# main.net
KiCad netlist of a schematic drawn in Altium Designer
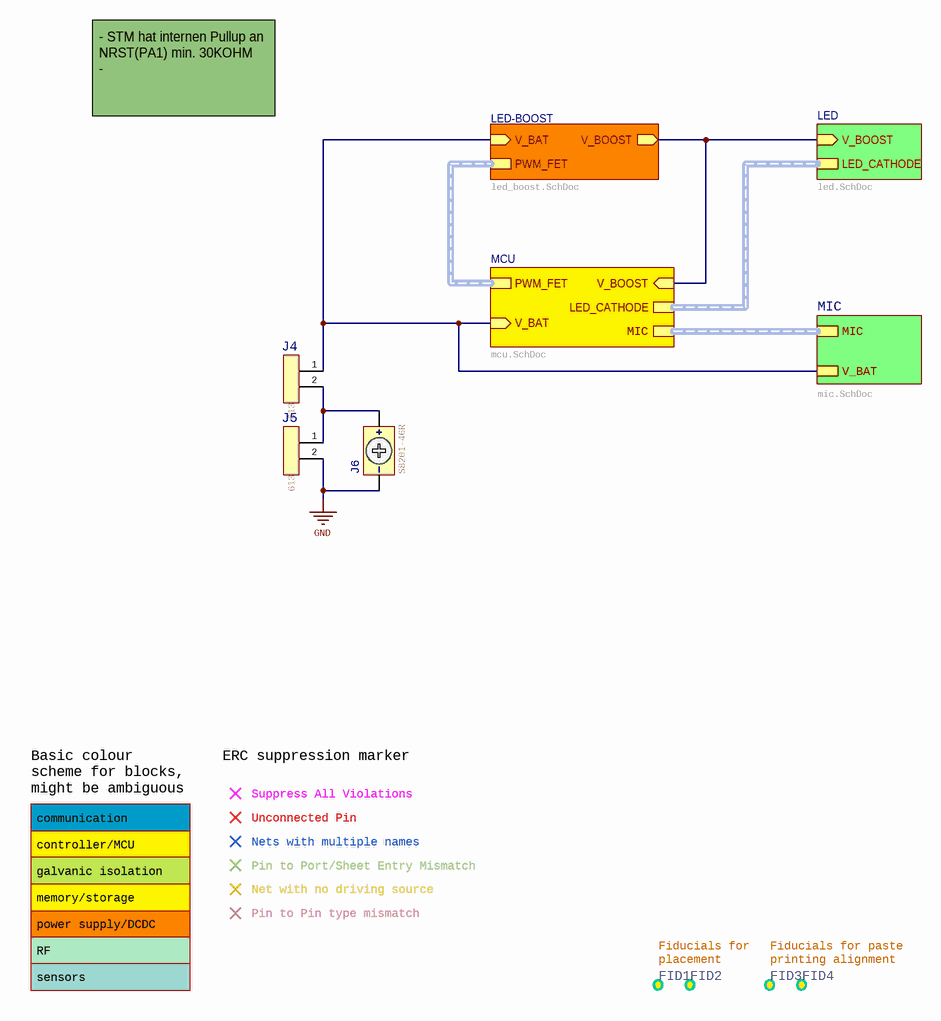
[diagram p0: main.SchDoc]

(export (version "E")
  (design (tool "Eeschema 10.0.6"))
  (components
    (comp (ref "FID1")
      (value "FIDUCIAL")
      (footprint "FID-1MM-0.5MM")
      (description "Fiducial Mark, 1mm diameter, 0.5mm clearance")
      (libsource (lib "Contronix") (part "FIDUCIAL"))
    )
    (comp (ref "FID2")
      (value "FIDUCIAL")
      (footprint "FID-1MM-0.5MM")
      (description "Fiducial Mark, 1mm diameter, 0.5mm clearance")
      (libsource (lib "Contronix") (part "FIDUCIAL"))
    )
    (comp (ref "FID3")
      (value "FIDUCIAL-CIRCLE-PASTE")
      (footprint "FID-1MM-0.5MM-PASTE")
      (description "Fiducial Mark, 1mm circle0.5mm clearance, Pastemask open")
      (libsource (lib "Contronix") (part "FIDUCIAL-CIRCLE-PASTE"))
    )
    (comp (ref "FID4")
      (value "FIDUCIAL-CIRCLE-PASTE")
      (footprint "FID-1MM-0.5MM-PASTE")
      (description "Fiducial Mark, 1mm circle0.5mm clearance, Pastemask open")
      (libsource (lib "Contronix") (part "FIDUCIAL-CIRCLE-PASTE"))
    )
    (comp (ref "J4")
      (value "CON-02")
      (footprint "CON-02-1-254-V-T-PFL-Jumper")
      (description "Stiftleiste, 2-polig, 2.54mm, +Jumper")
      (fields
        (field (name "MANUFACTURER P/N") "61300211121")
        (field (name "MANUFACTURER") "Würth Elektronik")
        (field (name "MANUFACTURER PART NUMBER") "61300211121")
      )
      (libsource (lib "Contronix") (part "CON-02"))
    )
    (comp (ref "J5")
      (value "CON-02")
      (footprint "CON-02-1-254-V-T-PFL-Jumper")
      (description "Stiftleiste, 2-polig, 2.54mm, +Jumper")
      (fields
        (field (name "MANUFACTURER P/N") "61300211121")
        (field (name "MANUFACTURER") "Würth Elektronik")
        (field (name "MANUFACTURER PART NUMBER") "61300211121")
      )
      (libsource (lib "Contronix") (part "CON-02"))
    )
    (comp (ref "J6")
      (value "BAT-COIN")
      (footprint "BAT-CR1225-SMD-HARWIN")
      (description "CR1216 1225 Battery Holder SMT")
      (fields
        (field (name "MANUFACTURER P/N") "S8201-46R")
        (field (name "MANUFACTURER") "Harwin")
        (field (name "MANUFACTURER PART NUMBER") "S8201-46R")
      )
      (libsource (lib "Contronix") (part "BAT-COIN"))
    )
  )
  (nets
    (net (code "4") (name "/V_BAT") (class "Default")
      (node (ref "J4") (pin "1") (pinfunction "1_1") (pintype "passive"))
    )
    (net (code "6") (name "GND") (class "Default")
      (node (ref "J5") (pin "2") (pinfunction "2_2") (pintype "passive"))
      (node (ref "J6") (pin "2") (pinfunction "-_2") (pintype "passive"))
    )
    (net (code "7") (name "Net-(J6-+)") (class "Default")
      (node (ref "J4") (pin "2") (pinfunction "2_2") (pintype "passive"))
      (node (ref "J5") (pin "1") (pinfunction "1_1") (pintype "passive"))
      (node (ref "J6") (pin "1") (pinfunction "+_1") (pintype "passive"))
    )
  )
)
